# Management.net
KiCad netlist of a schematic drawn in Altium Designer
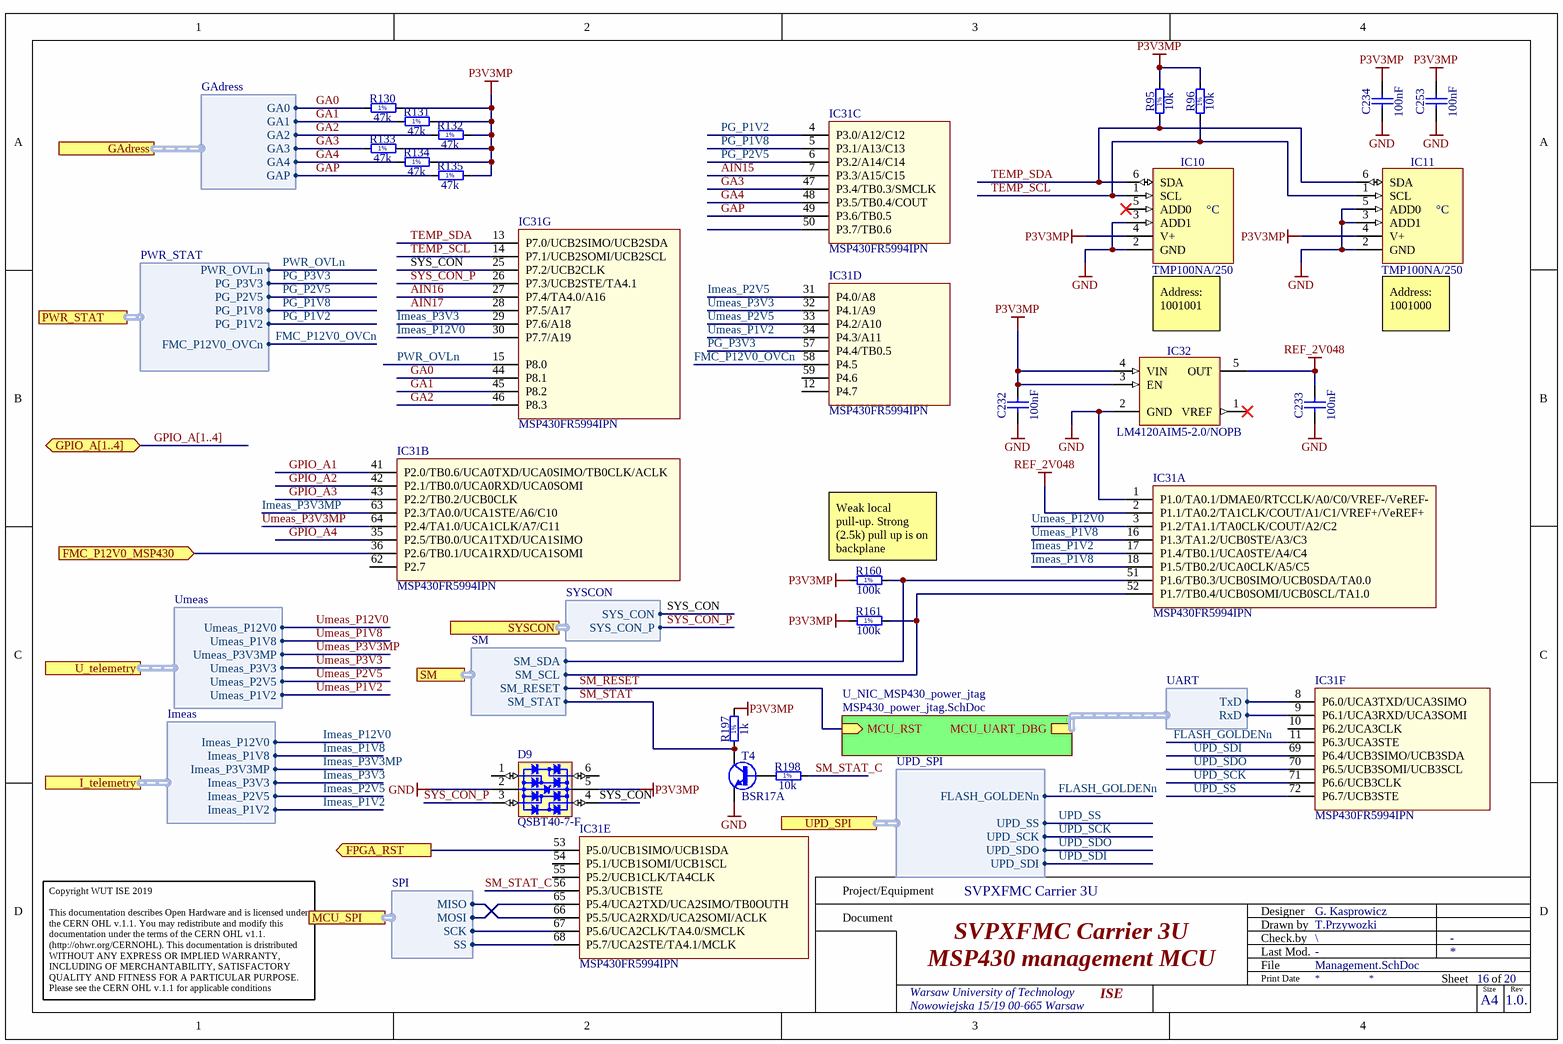
[diagram p0: Management.SchDoc]

(export (version "E")
  (design (tool "Eeschema 10.0.6"))
  (components
    (comp (ref "C232")
      (value "100nF")
      (footprint "CAPC1005X55N")
      (description "Non-polarised capacitor")
      (fields
        (field (name "PART NUMBER") "CC0402_100NF_25V_10%_X7R_YUDEN_TMK105B7104KVHF")
        (field (name "VOLTAGE") "25V")
        (field (name "AUTHOR") "CERN DEM JLC")
      )
      (libsource (lib "Capacitors") (part "Capacitor - non polarized"))
    )
    (comp (ref "C233")
      (value "100nF")
      (footprint "CAPC1005X55N")
      (description "Non-polarised capacitor")
      (fields
        (field (name "PART NUMBER") "CC0402_100NF_25V_10%_X7R_YUDEN_TMK105B7104KVHF")
        (field (name "VOLTAGE") "25V")
        (field (name "AUTHOR") "CERN DEM JLC")
      )
      (libsource (lib "Capacitors") (part "Capacitor - non polarized"))
    )
    (comp (ref "C234")
      (value "100nF")
      (footprint "CAPC1005X55N")
      (description "Non-polarised capacitor")
      (fields
        (field (name "PART NUMBER") "CC0402_100NF_25V_10%_X7R_YUDEN_TMK105B7104KVHF")
        (field (name "VOLTAGE") "25V")
        (field (name "AUTHOR") "CERN DEM JLC")
      )
      (libsource (lib "Capacitors") (part "Capacitor - non polarized"))
    )
    (comp (ref "C253")
      (value "100nF")
      (footprint "CAPC1005X55N")
      (description "Non-polarised capacitor")
      (fields
        (field (name "PART NUMBER") "CC0402_100NF_25V_10%_X7R_YUDEN_TMK105B7104KVHF")
        (field (name "VOLTAGE") "25V")
        (field (name "AUTHOR") "CERN DEM JLC")
      )
      (libsource (lib "Capacitors") (part "Capacitor - non polarized"))
    )
    (comp (ref "D9")
      (value "QSBT40-7-F")
      (footprint "SOT65P210X110-6N")
      (libsource (lib "LIBRARY_SCH") (part "D_TVS_QSBT40-7-F"))
    )
    (comp (ref "IC10")
      (value "TMP100NA/250")
      (footprint "SOT95P280X145-6N")
      (description "Digital Temperature Sensor with I2C Interface")
      (fields (field (name "MANUFACTURER") "TEXAS INSTRUMENTS") (field (name "AUTHOR") "CERN DEM JLC"))
      (libsource (lib "ICs And Semiconductors") (part "TMP100"))
    )
    (comp (ref "IC11")
      (value "TMP100NA/250")
      (footprint "SOT95P280X145-6N")
      (description "Digital Temperature Sensor with I2C Interface")
      (fields (field (name "MANUFACTURER") "TEXAS INSTRUMENTS") (field (name "AUTHOR") "CERN DEM JLC"))
      (libsource (lib "ICs And Semiconductors") (part "TMP100"))
    )
    (comp (ref "IC31")
      (value "MSP430FR5994IPN")
      (footprint "PQFP50P1400X1400-80N")
      (fields (field (name "MANUFACTURER") "TI"))
      (libsource (lib "ICs_And_Semiconductors") (part "MSP430FR5994IPN"))
    )
    (comp (ref "IC32")
      (value "LM4120AIM5-2.0/NOPB")
      (footprint "SOT95P280X145-5N")
      (description "Precision Micropower Low Dropout Voltage Reference")
      (fields (field (name "MANUFACTURER") "TEXAS INSTRUMENTS") (field (name "AUTHOR") "CERN DEM JMW"))
      (libsource (lib "ICs And Semiconductors") (part "LM4120"))
    )
    (comp (ref "R95")
      (value "10k")
      (footprint "RESC1005X40N")
      (description "Resistor - 1%")
      (fields
        (field (name "PART NUMBER") "R0402_10K_1%_0.0625W_100PPM")
        (field (name "POWER") "0.0625W")
        (field (name "AUTHOR") "CERN DEM JLC")
      )
      (libsource (lib "Resistors") (part "Resistor - 1%"))
    )
    (comp (ref "R96")
      (value "10k")
      (footprint "RESC1005X40N")
      (description "Resistor - 1%")
      (fields
        (field (name "PART NUMBER") "R0402_10K_1%_0.0625W_100PPM")
        (field (name "POWER") "0.0625W")
        (field (name "AUTHOR") "CERN DEM JLC")
      )
      (libsource (lib "Resistors") (part "Resistor - 1%"))
    )
    (comp (ref "R130")
      (value "47k")
      (footprint "RESC1005X40N")
      (description "Resistor - 1%")
      (fields
        (field (name "PART NUMBER") "R0402_47K_1%_0.0625W_100PPM")
        (field (name "POWER") "0.0625W")
        (field (name "AUTHOR") "CERN DEM JLC")
      )
      (libsource (lib "Resistors") (part "Resistor - 1%"))
    )
    (comp (ref "R131")
      (value "47k")
      (footprint "RESC1005X40N")
      (description "Resistor - 1%")
      (fields
        (field (name "PART NUMBER") "R0402_47K_1%_0.0625W_100PPM")
        (field (name "POWER") "0.0625W")
        (field (name "AUTHOR") "CERN DEM JLC")
      )
      (libsource (lib "Resistors") (part "Resistor - 1%"))
    )
    (comp (ref "R132")
      (value "47k")
      (footprint "RESC1005X40N")
      (description "Resistor - 1%")
      (fields
        (field (name "PART NUMBER") "R0402_47K_1%_0.0625W_100PPM")
        (field (name "POWER") "0.0625W")
        (field (name "AUTHOR") "CERN DEM JLC")
      )
      (libsource (lib "Resistors") (part "Resistor - 1%"))
    )
    (comp (ref "R133")
      (value "47k")
      (footprint "RESC1005X40N")
      (description "Resistor - 1%")
      (fields
        (field (name "PART NUMBER") "R0402_47K_1%_0.0625W_100PPM")
        (field (name "POWER") "0.0625W")
        (field (name "AUTHOR") "CERN DEM JLC")
      )
      (libsource (lib "Resistors") (part "Resistor - 1%"))
    )
    (comp (ref "R134")
      (value "47k")
      (footprint "RESC1005X40N")
      (description "Resistor - 1%")
      (fields
        (field (name "PART NUMBER") "R0402_47K_1%_0.0625W_100PPM")
        (field (name "POWER") "0.0625W")
        (field (name "AUTHOR") "CERN DEM JLC")
      )
      (libsource (lib "Resistors") (part "Resistor - 1%"))
    )
    (comp (ref "R135")
      (value "47k")
      (footprint "RESC1005X40N")
      (description "Resistor - 1%")
      (fields
        (field (name "PART NUMBER") "R0402_47K_1%_0.0625W_100PPM")
        (field (name "POWER") "0.0625W")
        (field (name "AUTHOR") "CERN DEM JLC")
      )
      (libsource (lib "Resistors") (part "Resistor - 1%"))
    )
    (comp (ref "R160")
      (value "100k")
      (footprint "RESC1005X40N")
      (description "Resistor - 1%")
      (fields
        (field (name "PART NUMBER") "R0402_100K_1%_0.0625W_100PPM")
        (field (name "POWER") "0.0625W")
        (field (name "AUTHOR") "CERN DEM JLC")
      )
      (libsource (lib "Resistors") (part "Resistor - 1%"))
    )
    (comp (ref "R161")
      (value "100k")
      (footprint "RESC1005X40N")
      (description "Resistor - 1%")
      (fields
        (field (name "PART NUMBER") "R0402_100K_1%_0.0625W_100PPM")
        (field (name "POWER") "0.0625W")
        (field (name "AUTHOR") "CERN DEM JLC")
      )
      (libsource (lib "Resistors") (part "Resistor - 1%"))
    )
    (comp (ref "R197")
      (value "1k")
      (footprint "RESC1005X40N")
      (description "Resistor - 1%")
      (fields
        (field (name "PART NUMBER") "R0402_1K_1%_0.0625W_100PPM")
        (field (name "POWER") "0.0625W")
        (field (name "AUTHOR") "CERN DEM JLC")
      )
      (libsource (lib "Resistors") (part "Resistor - 1%"))
    )
    (comp (ref "R198")
      (value "10k")
      (footprint "RESC1005X40N")
      (description "Resistor - 1%")
      (fields
        (field (name "PART NUMBER") "R0402_10K_1%_0.0625W_100PPM")
        (field (name "POWER") "0.0625W")
        (field (name "AUTHOR") "CERN DEM JLC")
      )
      (libsource (lib "Resistors") (part "Resistor - 1%"))
    )
    (comp (ref "T4")
      (value "BSR17A")
      (footprint "SOT95P240X110-3N")
      (description "NPN Transistor")
      (fields (field (name "MANUFACTURER") "FAIRCHILD SEMICONDUCTOR") (field (name "AUTHOR") "CERN DEM JLC"))
      (libsource (lib "ICs And Semiconductors") (part "NPN B1 E2 C3"))
    )
  )
  (nets
    (net (code "10") (name "/AIN15") (class "Default")
      (node (ref "IC31") (pin "7") (pinfunction "P3.3/A15/C15_7") (pintype "passive"))
    )
    (net (code "11") (name "/AIN16") (class "Default")
      (node (ref "IC31") (pin "27") (pinfunction "P7.4/TA4.0/A16_27") (pintype "passive"))
    )
    (net (code "12") (name "/AIN17") (class "Default")
      (node (ref "IC31") (pin "28") (pinfunction "P7.5/A17_28") (pintype "passive"))
    )
    (net (code "13") (name "/FLASH_GOLDENn") (class "Default")
      (node (ref "IC31") (pin "11") (pinfunction "P6.3/UCA3STE_11") (pintype "passive"))
    )
    (net (code "14") (name "/FMC_P12V0_MSP430") (class "Default")
      (node (ref "IC31") (pin "36") (pinfunction "P2.6/TB0.1/UCA1RXD/UCA1SOMI_36") (pintype "passive"))
    )
    (net (code "15") (name "/FMC_P12V0_OVCn") (class "Default")
      (node (ref "IC31") (pin "58") (pinfunction "P4.5_58") (pintype "passive"))
    )
    (net (code "16") (name "/FPGA_RST") (class "Default")
      (node (ref "IC31") (pin "53") (pinfunction "P5.0/UCB1SIMO/UCB1SDA_53") (pintype "passive"))
    )
    (net (code "17") (name "/GA0") (class "Default")
      (node (ref "IC31") (pin "44") (pinfunction "P8.1_44") (pintype "passive"))
      (node (ref "R130") (pin "1") (pinfunction "1_1") (pintype "passive"))
    )
    (net (code "18") (name "/GA1") (class "Default")
      (node (ref "IC31") (pin "45") (pinfunction "P8.2_45") (pintype "passive"))
      (node (ref "R131") (pin "1") (pinfunction "1_1") (pintype "passive"))
    )
    (net (code "19") (name "/GA2") (class "Default")
      (node (ref "IC31") (pin "46") (pinfunction "P8.3_46") (pintype "passive"))
      (node (ref "R132") (pin "1") (pinfunction "1_1") (pintype "passive"))
    )
    (net (code "20") (name "/GA3") (class "Default")
      (node (ref "IC31") (pin "47") (pinfunction "P3.4/TB0.3/SMCLK_47") (pintype "passive"))
      (node (ref "R133") (pin "1") (pinfunction "1_1") (pintype "passive"))
    )
    (net (code "21") (name "/GA4") (class "Default")
      (node (ref "IC31") (pin "48") (pinfunction "P3.5/TB0.4/COUT_48") (pintype "passive"))
      (node (ref "R134") (pin "1") (pinfunction "1_1") (pintype "passive"))
    )
    (net (code "22") (name "/GAP") (class "Default")
      (node (ref "IC31") (pin "49") (pinfunction "P3.6/TB0.5_49") (pintype "passive"))
      (node (ref "R135") (pin "1") (pinfunction "1_1") (pintype "passive"))
    )
    (net (code "23") (name "/GPIO_A1") (class "Default")
      (node (ref "IC31") (pin "41") (pinfunction "P2.0/TB0.6/UCA0TXD/UCA0SIMO/TB0CLK/ACLK_41") (pintype "passive"))
    )
    (net (code "24") (name "/GPIO_A2") (class "Default")
      (node (ref "IC31") (pin "42") (pinfunction "P2.1/TB0.0/UCA0RXD/UCA0SOMI_42") (pintype "passive"))
    )
    (net (code "25") (name "/GPIO_A3") (class "Default")
      (node (ref "IC31") (pin "43") (pinfunction "P2.2/TB0.2/UCB0CLK_43") (pintype "passive"))
    )
    (net (code "26") (name "/GPIO_A4") (class "Default")
      (node (ref "IC31") (pin "35") (pinfunction "P2.5/TB0.0/UCA1TXD/UCA1SIMO_35") (pintype "passive"))
    )
    (net (code "28") (name "/Imeas_P1V2") (class "Default")
      (node (ref "IC31") (pin "17") (pinfunction "P1.4/TB0.1/UCA0STE/A4/C4_17") (pintype "passive"))
    )
    (net (code "29") (name "/Imeas_P1V8") (class "Default")
      (node (ref "IC31") (pin "18") (pinfunction "P1.5/TB0.2/UCA0CLK/A5/C5_18") (pintype "passive"))
    )
    (net (code "30") (name "/Imeas_P2V5") (class "Default")
      (node (ref "IC31") (pin "31") (pinfunction "P4.0/A8_31") (pintype "passive"))
    )
    (net (code "31") (name "/Imeas_P3V3") (class "Default")
      (node (ref "IC31") (pin "29") (pinfunction "P7.6/A18_29") (pintype "passive"))
    )
    (net (code "32") (name "/Imeas_P3V3MP") (class "Default")
      (node (ref "IC31") (pin "63") (pinfunction "P2.3/TA0.0/UCA1STE/A6/C10_63") (pintype "passive"))
    )
    (net (code "33") (name "/Imeas_P12V0") (class "Default")
      (node (ref "IC31") (pin "30") (pinfunction "P7.7/A19_30") (pintype "passive"))
    )
    (net (code "34") (name "/MISO") (class "Default")
      (node (ref "IC31") (pin "66") (pinfunction "P5.5/UCA2RXD/UCA2SOMI/ACLK_66") (pintype "passive"))
    )
    (net (code "35") (name "/MOSI") (class "Default")
      (node (ref "IC31") (pin "65") (pinfunction "P5.4/UCA2TXD/UCA2SIMO/TB0OUTH_65") (pintype "passive"))
    )
    (net (code "36") (name "/PG_P1V2") (class "Default")
      (node (ref "IC31") (pin "4") (pinfunction "P3.0/A12/C12_4") (pintype "passive"))
    )
    (net (code "37") (name "/PG_P1V8") (class "Default")
      (node (ref "IC31") (pin "5") (pinfunction "P3.1/A13/C13_5") (pintype "passive"))
    )
    (net (code "38") (name "/PG_P2V5") (class "Default")
      (node (ref "IC31") (pin "6") (pinfunction "P3.2/A14/C14_6") (pintype "passive"))
    )
    (net (code "39") (name "/PG_P3V3") (class "Default")
      (node (ref "IC31") (pin "57") (pinfunction "P4.4/TB0.5_57") (pintype "passive"))
    )
    (net (code "40") (name "/PWR_OVLn") (class "Default")
      (node (ref "IC31") (pin "15") (pinfunction "P8.0_15") (pintype "passive"))
    )
    (net (code "41") (name "/RxD") (class "Default")
      (node (ref "IC31") (pin "9") (pinfunction "P6.1/UCA3RXD/UCA3SOMI_9") (pintype "passive"))
    )
    (net (code "42") (name "/SCK") (class "Default")
      (node (ref "IC31") (pin "67") (pinfunction "P5.6/UCA2CLK/TA4.0/SMCLK_67") (pintype "passive"))
    )
    (net (code "44") (name "/SM_SCL") (class "Default")
      (node (ref "IC31") (pin "52") (pinfunction "P1.7/TB0.4/UCB0SOMI/UCB0SCL/TA1.0_52") (pintype "passive"))
      (node (ref "R161") (pin "2") (pinfunction "2_2") (pintype "passive"))
    )
    (net (code "45") (name "/SM_SDA") (class "Default")
      (node (ref "IC31") (pin "51") (pinfunction "P1.6/TB0.3/UCB0SIMO/UCB0SDA/TA0.0_51") (pintype "passive"))
      (node (ref "R160") (pin "2") (pinfunction "2_2") (pintype "passive"))
    )
    (net (code "46") (name "/SM_STAT") (class "Default")
      (node (ref "R197") (pin "1") (pinfunction "1_1") (pintype "passive"))
      (node (ref "T4") (pin "3") (pinfunction "C_3") (pintype "passive"))
    )
    (net (code "47") (name "/SM_STAT_C") (class "Default")
      (node (ref "IC31") (pin "56") (pinfunction "P5.3/UCB1STE_56") (pintype "passive"))
      (node (ref "R198") (pin "2") (pinfunction "2_2") (pintype "passive"))
    )
    (net (code "48") (name "/SS") (class "Default")
      (node (ref "IC31") (pin "68") (pinfunction "P5.7/UCA2STE/TA4.1/MCLK_68") (pintype "passive"))
    )
    (net (code "49") (name "/SYS_CON") (class "Default")
      (node (ref "D9") (pin "4") (pinfunction "I/O3_4") (pintype "bidirectional"))
      (node (ref "IC31") (pin "25") (pinfunction "P7.2/UCB2CLK_25") (pintype "passive"))
    )
    (net (code "50") (name "/SYS_CON_P") (class "Default")
      (node (ref "D9") (pin "3") (pinfunction "I/O2_3") (pintype "bidirectional"))
      (node (ref "IC31") (pin "26") (pinfunction "P7.3/UCB2STE/TA4.1_26") (pintype "passive"))
    )
    (net (code "51") (name "/TEMP_SCL") (class "Default")
      (node (ref "IC10") (pin "1") (pinfunction "SCL_1") (pintype "input"))
      (node (ref "IC11") (pin "1") (pinfunction "SCL_1") (pintype "input"))
      (node (ref "IC31") (pin "14") (pinfunction "P7.1/UCB2SOMI/UCB2SCL_14") (pintype "passive"))
      (node (ref "R96") (pin "1") (pinfunction "1_1") (pintype "passive"))
    )
    (net (code "52") (name "/TEMP_SDA") (class "Default")
      (node (ref "IC10") (pin "6") (pinfunction "SDA_6") (pintype "bidirectional"))
      (node (ref "IC11") (pin "6") (pinfunction "SDA_6") (pintype "bidirectional"))
      (node (ref "IC31") (pin "13") (pinfunction "P7.0/UCB2SIMO/UCB2SDA_13") (pintype "passive"))
      (node (ref "R95") (pin "1") (pinfunction "1_1") (pintype "passive"))
    )
    (net (code "53") (name "/TxD") (class "Default")
      (node (ref "IC31") (pin "8") (pinfunction "P6.0/UCA3TXD/UCA3SIMO_8") (pintype "passive"))
    )
    (net (code "54") (name "/UPD_SCK") (class "Default")
      (node (ref "IC31") (pin "71") (pinfunction "P6.6/UCB3CLK_71") (pintype "passive"))
    )
    (net (code "55") (name "/UPD_SDI") (class "Default")
      (node (ref "IC31") (pin "69") (pinfunction "P6.4/UCB3SIMO/UCB3SDA_69") (pintype "passive"))
    )
    (net (code "56") (name "/UPD_SDO") (class "Default")
      (node (ref "IC31") (pin "70") (pinfunction "P6.5/UCB3SOMI/UCB3SCL_70") (pintype "passive"))
    )
    (net (code "57") (name "/UPD_SS") (class "Default")
      (node (ref "IC31") (pin "72") (pinfunction "P6.7/UCB3STE_72") (pintype "passive"))
    )
    (net (code "58") (name "/Umeas_P1V2") (class "Default")
      (node (ref "IC31") (pin "34") (pinfunction "P4.3/A11_34") (pintype "passive"))
    )
    (net (code "59") (name "/Umeas_P1V8") (class "Default")
      (node (ref "IC31") (pin "16") (pinfunction "P1.3/TA1.2/UCB0STE/A3/C3_16") (pintype "passive"))
    )
    (net (code "60") (name "/Umeas_P2V5") (class "Default")
      (node (ref "IC31") (pin "33") (pinfunction "P4.2/A10_33") (pintype "passive"))
    )
    (net (code "61") (name "/Umeas_P3V3") (class "Default")
      (node (ref "IC31") (pin "32") (pinfunction "P4.1/A9_32") (pintype "passive"))
    )
    (net (code "62") (name "/Umeas_P3V3MP") (class "Default")
      (node (ref "IC31") (pin "64") (pinfunction "P2.4/TA1.0/UCA1CLK/A7/C11_64") (pintype "passive"))
    )
    (net (code "63") (name "/Umeas_P12V0") (class "Default")
      (node (ref "IC31") (pin "3") (pinfunction "P1.2/TA1.1/TA0CLK/COUT/A2/C2_3") (pintype "passive"))
    )
    (net (code "73") (name "GND") (class "Default")
      (node (ref "C232") (pin "1") (pinfunction "1_1") (pintype "passive"))
      (node (ref "C233") (pin "1") (pinfunction "1_1") (pintype "passive"))
      (node (ref "C234") (pin "1") (pinfunction "1_1") (pintype "passive"))
      (node (ref "C253") (pin "1") (pinfunction "1_1") (pintype "passive"))
      (node (ref "D9") (pin "2") (pinfunction "GND_2") (pintype "power_in"))
      (node (ref "IC10") (pin "2") (pinfunction "GND_2") (pintype "power_in"))
      (node (ref "IC10") (pin "3") (pinfunction "ADD1_3") (pintype "input"))
      (node (ref "IC11") (pin "2") (pinfunction "GND_2") (pintype "power_in"))
      (node (ref "IC11") (pin "3") (pinfunction "ADD1_3") (pintype "input"))
      (node (ref "IC11") (pin "5") (pinfunction "ADD0_5") (pintype "input"))
      (node (ref "IC31") (pin "1") (pinfunction "P1.0/TA0.1/DMAE0/RTCCLK/A0/C0/VREF-/VeREF-_1") (pintype "passive"))
      (node (ref "IC32") (pin "2") (pinfunction "GND_2") (pintype "power_in"))
      (node (ref "T4") (pin "2") (pinfunction "E_2") (pintype "passive"))
    )
    (net (code "74") (name "Net-(T4-B)") (class "Default")
      (node (ref "R198") (pin "1") (pinfunction "1_1") (pintype "passive"))
      (node (ref "T4") (pin "1") (pinfunction "B_1") (pintype "passive"))
    )
    (net (code "75") (name "P3V3MP") (class "Default")
      (node (ref "C232") (pin "2") (pinfunction "2_2") (pintype "passive"))
      (node (ref "C234") (pin "2") (pinfunction "2_2") (pintype "passive"))
      (node (ref "C253") (pin "2") (pinfunction "2_2") (pintype "passive"))
      (node (ref "D9") (pin "5") (pinfunction "VBUS_5") (pintype "power_in"))
      (node (ref "IC10") (pin "4") (pinfunction "V+_4") (pintype "power_in"))
      (node (ref "IC11") (pin "4") (pinfunction "V+_4") (pintype "power_in"))
      (node (ref "IC32") (pin "3") (pinfunction "EN_3") (pintype "input"))
      (node (ref "IC32") (pin "4") (pinfunction "VIN_4") (pintype "input"))
      (node (ref "R130") (pin "2") (pinfunction "2_2") (pintype "passive"))
      (node (ref "R131") (pin "2") (pinfunction "2_2") (pintype "passive"))
      (node (ref "R132") (pin "2") (pinfunction "2_2") (pintype "passive"))
      (node (ref "R133") (pin "2") (pinfunction "2_2") (pintype "passive"))
      (node (ref "R134") (pin "2") (pinfunction "2_2") (pintype "passive"))
      (node (ref "R135") (pin "2") (pinfunction "2_2") (pintype "passive"))
      (node (ref "R160") (pin "1") (pinfunction "1_1") (pintype "passive"))
      (node (ref "R161") (pin "1") (pinfunction "1_1") (pintype "passive"))
      (node (ref "R197") (pin "2") (pinfunction "2_2") (pintype "passive"))
      (node (ref "R95") (pin "2") (pinfunction "2_2") (pintype "passive"))
      (node (ref "R96") (pin "2") (pinfunction "2_2") (pintype "passive"))
    )
    (net (code "76") (name "REF_2V048") (class "Default")
      (node (ref "C233") (pin "2") (pinfunction "2_2") (pintype "passive"))
      (node (ref "IC31") (pin "2") (pinfunction "P1.1/TA0.2/TA1CLK/COUT/A1/C1/VREF+/VeREF+_2") (pintype "passive"))
      (node (ref "IC32") (pin "5") (pinfunction "OUT_5") (pintype "power_in"))
    )
    (net (code "77") (name "unconnected-(D9-I{slash}O1-Pad1)") (class "Default")
      (node (ref "D9") (pin "1") (pinfunction "I/O1_1") (pintype "bidirectional"))
    )
    (net (code "78") (name "unconnected-(D9-I{slash}O4-Pad6)") (class "Default")
      (node (ref "D9") (pin "6") (pinfunction "I/O4_6") (pintype "bidirectional"))
    )
    (net (code "79") (name "unconnected-(IC10-ADD0-Pad5)") (class "Default")
      (node (ref "IC10") (pin "5") (pinfunction "ADD0_5") (pintype "input+no_connect"))
    )
    (net (code "80") (name "unconnected-(IC31B-P2.7-Pad62)") (class "Default")
      (node (ref "IC31") (pin "62") (pinfunction "P2.7_62") (pintype "passive"))
    )
    (net (code "81") (name "unconnected-(IC31C-P3.7{slash}TB0.6-Pad50)") (class "Default")
      (node (ref "IC31") (pin "50") (pinfunction "P3.7/TB0.6_50") (pintype "passive"))
    )
    (net (code "82") (name "unconnected-(IC31D-P4.6-Pad59)") (class "Default")
      (node (ref "IC31") (pin "59") (pinfunction "P4.6_59") (pintype "passive"))
    )
    (net (code "83") (name "unconnected-(IC31D-P4.7-Pad12)") (class "Default")
      (node (ref "IC31") (pin "12") (pinfunction "P4.7_12") (pintype "passive"))
    )
    (net (code "84") (name "unconnected-(IC31E-P5.1{slash}UCB1SOMI{slash}UCB1SCL-Pad54)") (class "Default")
      (node (ref "IC31") (pin "54") (pinfunction "P5.1/UCB1SOMI/UCB1SCL_54") (pintype "passive"))
    )
    (net (code "85") (name "unconnected-(IC31E-P5.2{slash}UCB1CLK{slash}TA4CLK-Pad55)") (class "Default")
      (node (ref "IC31") (pin "55") (pinfunction "P5.2/UCB1CLK/TA4CLK_55") (pintype "passive"))
    )
    (net (code "86") (name "unconnected-(IC31F-P6.2{slash}UCA3CLK-Pad10)") (class "Default")
      (node (ref "IC31") (pin "10") (pinfunction "P6.2/UCA3CLK_10") (pintype "passive"))
    )
    (net (code "87") (name "unconnected-(IC32-VREF-Pad1)") (class "Default")
      (node (ref "IC32") (pin "1") (pinfunction "VREF_1") (pintype "output+no_connect"))
    )
  )
)
